# ESP32.net
KiCad netlist of a schematic drawn in Altium Designer
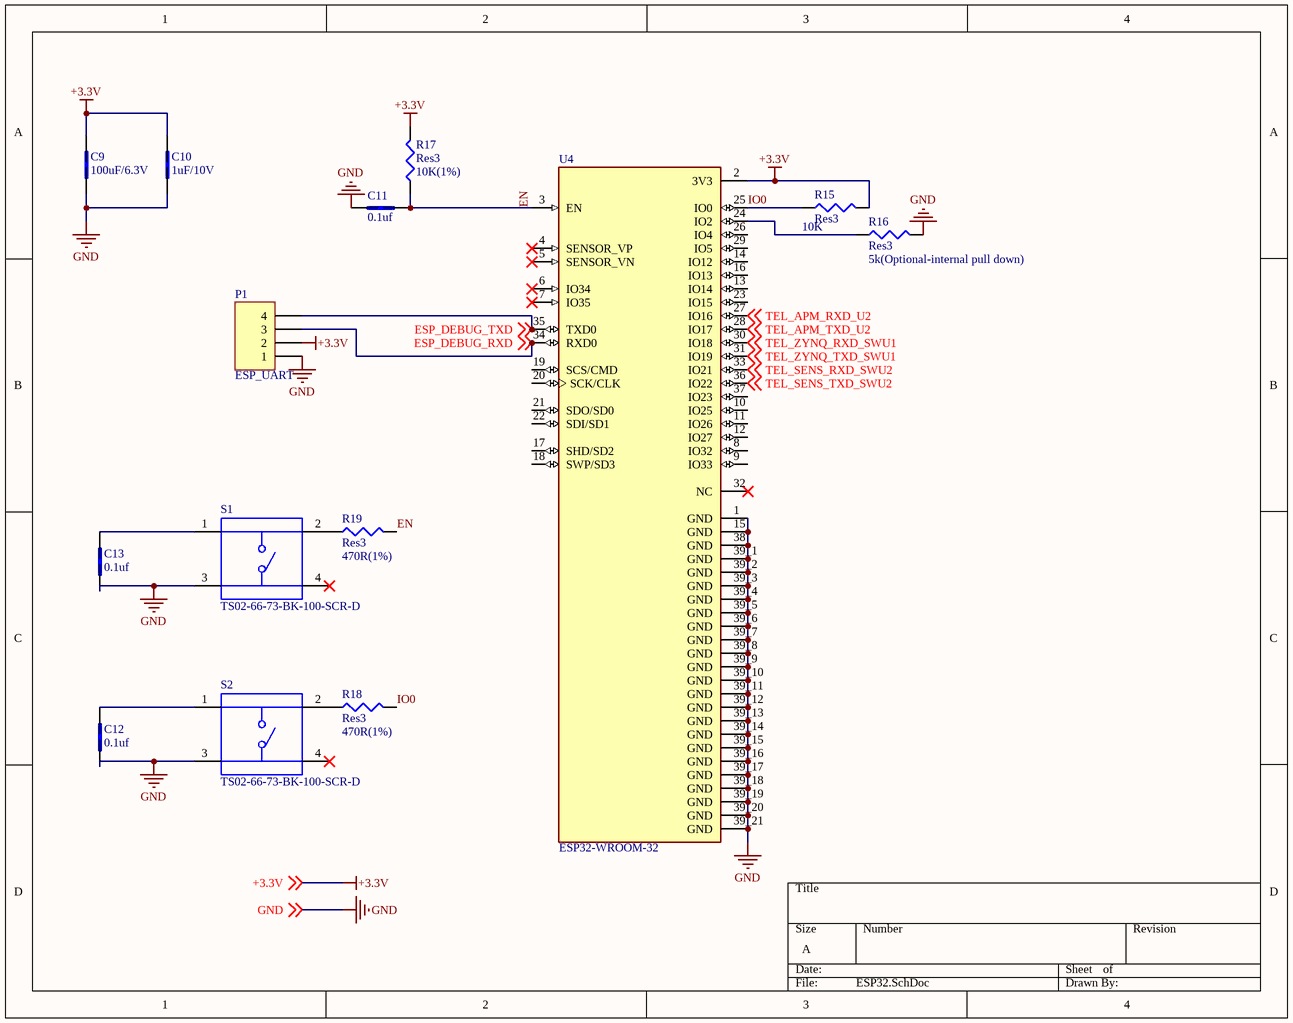
[diagram p0: ESP32.SchDoc]

(export (version "E")
  (design (tool "Eeschema 10.0.6"))
  (components
    (comp (ref "C9")
      (value "100uF/6.3V")
      (footprint "CAPC1608X90")
      (description "0.1ÂµF Â±10% 50V Ceramic Capacitor X7R 0603 (1608 Metric)")
      (fields (field (name "MP") "C0603C104K5RACTU") (field (name "DIGI-KEY_PART_NUMBER") "399-5089-1-ND"))
      (libsource (lib "C0603C104K5RACTU") (part "C0603C104K5RACTU"))
    )
    (comp (ref "C10")
      (value "1uF/10V")
      (footprint "CAPC1608X90")
      (description "0.1ÂµF Â±10% 50V Ceramic Capacitor X7R 0603 (1608 Metric)")
      (fields (field (name "MP") "C0603C104K5RACTU") (field (name "DIGI-KEY_PART_NUMBER") "399-5089-1-ND"))
      (libsource (lib "C0603C104K5RACTU") (part "C0603C104K5RACTU"))
    )
    (comp (ref "C11")
      (value "0.1uf")
      (footprint "CAPC1608X90")
      (description "0.1ÂµF Â±10% 50V Ceramic Capacitor X7R 0603 (1608 Metric)")
      (fields (field (name "MP") "C0603C104K5RACTU") (field (name "DIGI-KEY_PART_NUMBER") "399-5089-1-ND"))
      (libsource (lib "") (part "C0603C104K5RACTU_2"))
    )
    (comp (ref "C12")
      (value "0.1uf")
      (footprint "CAPC1608X90")
      (description "0.1ÂµF Â±10% 50V Ceramic Capacitor X7R 0603 (1608 Metric)")
      (fields (field (name "MP") "C0603C104K5RACTU") (field (name "DIGI-KEY_PART_NUMBER") "399-5089-1-ND"))
      (libsource (lib "") (part "C0603C104K5RACTU_1"))
    )
    (comp (ref "C13")
      (value "0.1uf")
      (footprint "CAPC1608X90")
      (description "0.1ÂµF Â±10% 50V Ceramic Capacitor X7R 0603 (1608 Metric)")
      (fields (field (name "MP") "C0603C104K5RACTU") (field (name "DIGI-KEY_PART_NUMBER") "399-5089-1-ND"))
      (libsource (lib "") (part "C0603C104K5RACTU_1"))
    )
    (comp (ref "P1")
      (value "ESP_UART")
      (footprint "HDR1X4")
      (description "Header, 4-Pin")
      (fields (field (name "PUBLISHER") "Altium Limited"))
      (libsource (lib "Miscellaneous Connectors") (part "Header 4"))
    )
    (comp (ref "R15")
      (value "Res3")
      (footprint "J1-0603")
      (description "Resistor")
      (fields (field (name "ALTIUM_VALUE") "10K") (field (name "PUBLISHER") "Altium Limited"))
      (libsource (lib "Miscellaneous Devices") (part "Res3"))
    )
    (comp (ref "R16")
      (value "Res3")
      (footprint "J1-0603")
      (description "Resistor")
      (fields
        (field (name "ALTIUM_VALUE") "5k(Optional-internal pull down)")
        (field (name "PUBLISHER") "Altium Limited")
      )
      (libsource (lib "Miscellaneous Devices") (part "Res3"))
    )
    (comp (ref "R17")
      (value "Res3")
      (footprint "J1-0603")
      (description "Resistor")
      (fields (field (name "ALTIUM_VALUE") "10K(1%)") (field (name "PUBLISHER") "Altium Limited"))
      (libsource (lib "Miscellaneous Devices") (part "Res3"))
    )
    (comp (ref "R18")
      (value "Res3")
      (footprint "J1-0603")
      (description "Resistor")
      (fields (field (name "ALTIUM_VALUE") "470R(1%)") (field (name "PUBLISHER") "Altium Limited"))
      (libsource (lib "Miscellaneous Devices") (part "Res3"))
    )
    (comp (ref "R19")
      (value "Res3")
      (footprint "J1-0603")
      (description "Resistor")
      (fields (field (name "ALTIUM_VALUE") "470R(1%)") (field (name "PUBLISHER") "Altium Limited"))
      (libsource (lib "Miscellaneous Devices") (part "Res3"))
    )
    (comp (ref "S1")
      (value "TS02-66-73-BK-100-SCR-D")
      (footprint "SW_TS02-66-73-BK-100-SCR-D")
      (fields (field (name "MF") "{'manufacturer': u'CUI'}"))
      (libsource (lib "TS02-66-73-BK-100-SCR-D") (part "TS02-66-73-BK-100-SCR-D"))
    )
    (comp (ref "S2")
      (value "TS02-66-73-BK-100-SCR-D")
      (footprint "SW_TS02-66-73-BK-100-SCR-D")
      (fields (field (name "MF") "{'manufacturer': u'CUI'}"))
      (libsource (lib "TS02-66-73-BK-100-SCR-D") (part "TS02-66-73-BK-100-SCR-D"))
    )
    (comp (ref "U4")
      (value "ESP32-WROOM-32")
      (footprint "MODULE_ESP32-WROOM-32")
      (libsource (lib "ESP32-WROOM-32") (part "ESP32-WROOM-32"))
    )
  )
  (nets
    (net (code "1") (name "+3.3V") (class "Default")
      (node (ref "C10") (pin "2") (pinfunction "2_2") (pintype "passive"))
      (node (ref "C9") (pin "2") (pinfunction "2_2") (pintype "passive"))
      (node (ref "P1") (pin "2") (pinfunction "2_2") (pintype "passive"))
      (node (ref "R15") (pin "2") (pinfunction "2_2") (pintype "passive"))
      (node (ref "R17") (pin "2") (pinfunction "2_2") (pintype "passive"))
      (node (ref "U4") (pin "2") (pinfunction "3V3_2") (pintype "power_in"))
    )
    (net (code "2") (name "/EN") (class "Default")
      (node (ref "C11") (pin "1") (pinfunction "1_1") (pintype "passive"))
      (node (ref "R17") (pin "1") (pinfunction "1_1") (pintype "passive"))
      (node (ref "R19") (pin "2") (pinfunction "2_2") (pintype "passive"))
      (node (ref "U4") (pin "3") (pinfunction "EN_3") (pintype "input"))
    )
    (net (code "3") (name "/IO0") (class "Default")
      (node (ref "R15") (pin "1") (pinfunction "1_1") (pintype "passive"))
      (node (ref "R18") (pin "2") (pinfunction "2_2") (pintype "passive"))
      (node (ref "U4") (pin "25") (pinfunction "IO0_25") (pintype "bidirectional"))
    )
    (net (code "4") (name "ESP_DEBUG_RXD") (class "Default")
      (node (ref "P1") (pin "3") (pinfunction "3_3") (pintype "passive"))
      (node (ref "U4") (pin "34") (pinfunction "RXD0_34") (pintype "bidirectional"))
    )
    (net (code "5") (name "ESP_DEBUG_TXD") (class "Default")
      (node (ref "P1") (pin "4") (pinfunction "4_4") (pintype "passive"))
      (node (ref "U4") (pin "35") (pinfunction "TXD0_35") (pintype "bidirectional"))
    )
    (net (code "6") (name "GND") (class "Default")
      (node (ref "C10") (pin "1") (pinfunction "1_1") (pintype "passive"))
      (node (ref "C11") (pin "2") (pinfunction "2_2") (pintype "passive"))
      (node (ref "C12") (pin "2") (pinfunction "2_2") (pintype "passive"))
      (node (ref "C13") (pin "2") (pinfunction "2_2") (pintype "passive"))
      (node (ref "C9") (pin "1") (pinfunction "1_1") (pintype "passive"))
      (node (ref "P1") (pin "1") (pinfunction "1_1") (pintype "passive"))
      (node (ref "R16") (pin "2") (pinfunction "2_2") (pintype "passive"))
      (node (ref "S1") (pin "3") (pinfunction "3_3") (pintype "passive"))
      (node (ref "S2") (pin "3") (pinfunction "3_3") (pintype "passive"))
      (node (ref "U4") (pin "1") (pinfunction "GND_1") (pintype "power_in"))
      (node (ref "U4") (pin "15") (pinfunction "GND_15") (pintype "power_in"))
      (node (ref "U4") (pin "38") (pinfunction "GND_38") (pintype "power_in"))
      (node (ref "U4") (pin "39_1") (pinfunction "GND_39_1") (pintype "power_in"))
      (node (ref "U4") (pin "39_10") (pinfunction "GND_39_10") (pintype "power_in"))
      (node (ref "U4") (pin "39_11") (pinfunction "GND_39_11") (pintype "power_in"))
      (node (ref "U4") (pin "39_12") (pinfunction "GND_39_12") (pintype "power_in"))
      (node (ref "U4") (pin "39_13") (pinfunction "GND_39_13") (pintype "power_in"))
      (node (ref "U4") (pin "39_14") (pinfunction "GND_39_14") (pintype "power_in"))
      (node (ref "U4") (pin "39_15") (pinfunction "GND_39_15") (pintype "power_in"))
      (node (ref "U4") (pin "39_16") (pinfunction "GND_39_16") (pintype "power_in"))
      (node (ref "U4") (pin "39_17") (pinfunction "GND_39_17") (pintype "power_in"))
      (node (ref "U4") (pin "39_18") (pinfunction "GND_39_18") (pintype "power_in"))
      (node (ref "U4") (pin "39_19") (pinfunction "GND_39_19") (pintype "power_in"))
      (node (ref "U4") (pin "39_2") (pinfunction "GND_39_2") (pintype "power_in"))
      (node (ref "U4") (pin "39_20") (pinfunction "GND_39_20") (pintype "power_in"))
      (node (ref "U4") (pin "39_21") (pinfunction "GND_39_21") (pintype "power_in"))
      (node (ref "U4") (pin "39_3") (pinfunction "GND_39_3") (pintype "power_in"))
      (node (ref "U4") (pin "39_4") (pinfunction "GND_39_4") (pintype "power_in"))
      (node (ref "U4") (pin "39_5") (pinfunction "GND_39_5") (pintype "power_in"))
      (node (ref "U4") (pin "39_6") (pinfunction "GND_39_6") (pintype "power_in"))
      (node (ref "U4") (pin "39_7") (pinfunction "GND_39_7") (pintype "power_in"))
      (node (ref "U4") (pin "39_8") (pinfunction "GND_39_8") (pintype "power_in"))
      (node (ref "U4") (pin "39_9") (pinfunction "GND_39_9") (pintype "power_in"))
    )
    (net (code "7") (name "Net-(C12-Pad1)") (class "Default")
      (node (ref "C12") (pin "1") (pinfunction "1_1") (pintype "passive"))
      (node (ref "S2") (pin "1") (pinfunction "1_1") (pintype "passive"))
    )
    (net (code "8") (name "Net-(C13-Pad1)") (class "Default")
      (node (ref "C13") (pin "1") (pinfunction "1_1") (pintype "passive"))
      (node (ref "S1") (pin "1") (pinfunction "1_1") (pintype "passive"))
    )
    (net (code "9") (name "Net-(R18-Pad1)") (class "Default")
      (node (ref "R18") (pin "1") (pinfunction "1_1") (pintype "passive"))
      (node (ref "S2") (pin "2") (pinfunction "2_2") (pintype "passive"))
    )
    (net (code "10") (name "Net-(R19-Pad1)") (class "Default")
      (node (ref "R19") (pin "1") (pinfunction "1_1") (pintype "passive"))
      (node (ref "S1") (pin "2") (pinfunction "2_2") (pintype "passive"))
    )
    (net (code "11") (name "Net-(U4-IO2)") (class "Default")
      (node (ref "R16") (pin "1") (pinfunction "1_1") (pintype "passive"))
      (node (ref "U4") (pin "24") (pinfunction "IO2_24") (pintype "bidirectional"))
    )
    (net (code "12") (name "TEL_APM_RXD_U2") (class "Default")
      (node (ref "U4") (pin "27") (pinfunction "IO16_27") (pintype "bidirectional"))
    )
    (net (code "13") (name "TEL_APM_TXD_U2") (class "Default")
      (node (ref "U4") (pin "28") (pinfunction "IO17_28") (pintype "bidirectional"))
    )
    (net (code "14") (name "TEL_SENS_RXD_SWU2") (class "Default")
      (node (ref "U4") (pin "33") (pinfunction "IO21_33") (pintype "bidirectional"))
    )
    (net (code "15") (name "TEL_SENS_TXD_SWU2") (class "Default")
      (node (ref "U4") (pin "36") (pinfunction "IO22_36") (pintype "bidirectional"))
    )
    (net (code "16") (name "TEL_ZYNQ_RXD_SWU1") (class "Default")
      (node (ref "U4") (pin "30") (pinfunction "IO18_30") (pintype "bidirectional"))
    )
    (net (code "17") (name "TEL_ZYNQ_TXD_SWU1") (class "Default")
      (node (ref "U4") (pin "31") (pinfunction "IO19_31") (pintype "bidirectional"))
    )
    (net (code "18") (name "unconnected-(S1-Pad4)") (class "Default")
      (node (ref "S1") (pin "4") (pinfunction "4_4") (pintype "passive+no_connect"))
    )
    (net (code "19") (name "unconnected-(S2-Pad4)") (class "Default")
      (node (ref "S2") (pin "4") (pinfunction "4_4") (pintype "passive+no_connect"))
    )
    (net (code "20") (name "unconnected-(U4-IO4-Pad26)") (class "Default")
      (node (ref "U4") (pin "26") (pinfunction "IO4_26") (pintype "bidirectional"))
    )
    (net (code "21") (name "unconnected-(U4-IO5-Pad29)") (class "Default")
      (node (ref "U4") (pin "29") (pinfunction "IO5_29") (pintype "bidirectional"))
    )
    (net (code "22") (name "unconnected-(U4-IO12-Pad14)") (class "Default")
      (node (ref "U4") (pin "14") (pinfunction "IO12_14") (pintype "bidirectional"))
    )
    (net (code "23") (name "unconnected-(U4-IO13-Pad16)") (class "Default")
      (node (ref "U4") (pin "16") (pinfunction "IO13_16") (pintype "bidirectional"))
    )
    (net (code "24") (name "unconnected-(U4-IO14-Pad13)") (class "Default")
      (node (ref "U4") (pin "13") (pinfunction "IO14_13") (pintype "bidirectional"))
    )
    (net (code "25") (name "unconnected-(U4-IO15-Pad23)") (class "Default")
      (node (ref "U4") (pin "23") (pinfunction "IO15_23") (pintype "bidirectional"))
    )
    (net (code "26") (name "unconnected-(U4-IO23-Pad37)") (class "Default")
      (node (ref "U4") (pin "37") (pinfunction "IO23_37") (pintype "bidirectional"))
    )
    (net (code "27") (name "unconnected-(U4-IO25-Pad10)") (class "Default")
      (node (ref "U4") (pin "10") (pinfunction "IO25_10") (pintype "bidirectional"))
    )
    (net (code "28") (name "unconnected-(U4-IO26-Pad11)") (class "Default")
      (node (ref "U4") (pin "11") (pinfunction "IO26_11") (pintype "bidirectional"))
    )
    (net (code "29") (name "unconnected-(U4-IO27-Pad12)") (class "Default")
      (node (ref "U4") (pin "12") (pinfunction "IO27_12") (pintype "bidirectional"))
    )
    (net (code "30") (name "unconnected-(U4-IO32-Pad8)") (class "Default")
      (node (ref "U4") (pin "8") (pinfunction "IO32_8") (pintype "bidirectional"))
    )
    (net (code "31") (name "unconnected-(U4-IO33-Pad9)") (class "Default")
      (node (ref "U4") (pin "9") (pinfunction "IO33_9") (pintype "bidirectional"))
    )
    (net (code "32") (name "unconnected-(U4-IO34-Pad6)") (class "Default")
      (node (ref "U4") (pin "6") (pinfunction "IO34_6") (pintype "input+no_connect"))
    )
    (net (code "33") (name "unconnected-(U4-IO35-Pad7)") (class "Default")
      (node (ref "U4") (pin "7") (pinfunction "IO35_7") (pintype "input+no_connect"))
    )
    (net (code "34") (name "unconnected-(U4-NC-Pad32)") (class "Default")
      (node (ref "U4") (pin "32") (pinfunction "NC_32") (pintype "passive+no_connect"))
    )
    (net (code "35") (name "unconnected-(U4-SCK{slash}CLK-Pad20)") (class "Default")
      (node (ref "U4") (pin "20") (pinfunction "SCK/CLK_20") (pintype "bidirectional"))
    )
    (net (code "36") (name "unconnected-(U4-SCS{slash}CMD-Pad19)") (class "Default")
      (node (ref "U4") (pin "19") (pinfunction "SCS/CMD_19") (pintype "bidirectional"))
    )
    (net (code "37") (name "unconnected-(U4-SDI{slash}SD1-Pad22)") (class "Default")
      (node (ref "U4") (pin "22") (pinfunction "SDI/SD1_22") (pintype "bidirectional"))
    )
    (net (code "38") (name "unconnected-(U4-SDO{slash}SD0-Pad21)") (class "Default")
      (node (ref "U4") (pin "21") (pinfunction "SDO/SD0_21") (pintype "bidirectional"))
    )
    (net (code "39") (name "unconnected-(U4-SENSOR_VN-Pad5)") (class "Default")
      (node (ref "U4") (pin "5") (pinfunction "SENSOR_VN_5") (pintype "input+no_connect"))
    )
    (net (code "40") (name "unconnected-(U4-SENSOR_VP-Pad4)") (class "Default")
      (node (ref "U4") (pin "4") (pinfunction "SENSOR_VP_4") (pintype "input+no_connect"))
    )
    (net (code "41") (name "unconnected-(U4-SHD{slash}SD2-Pad17)") (class "Default")
      (node (ref "U4") (pin "17") (pinfunction "SHD/SD2_17") (pintype "bidirectional"))
    )
    (net (code "42") (name "unconnected-(U4-SWP{slash}SD3-Pad18)") (class "Default")
      (node (ref "U4") (pin "18") (pinfunction "SWP/SD3_18") (pintype "bidirectional"))
    )
  )
)
